# 01_POWER.net
KiCad netlist of a schematic drawn in Altium Designer
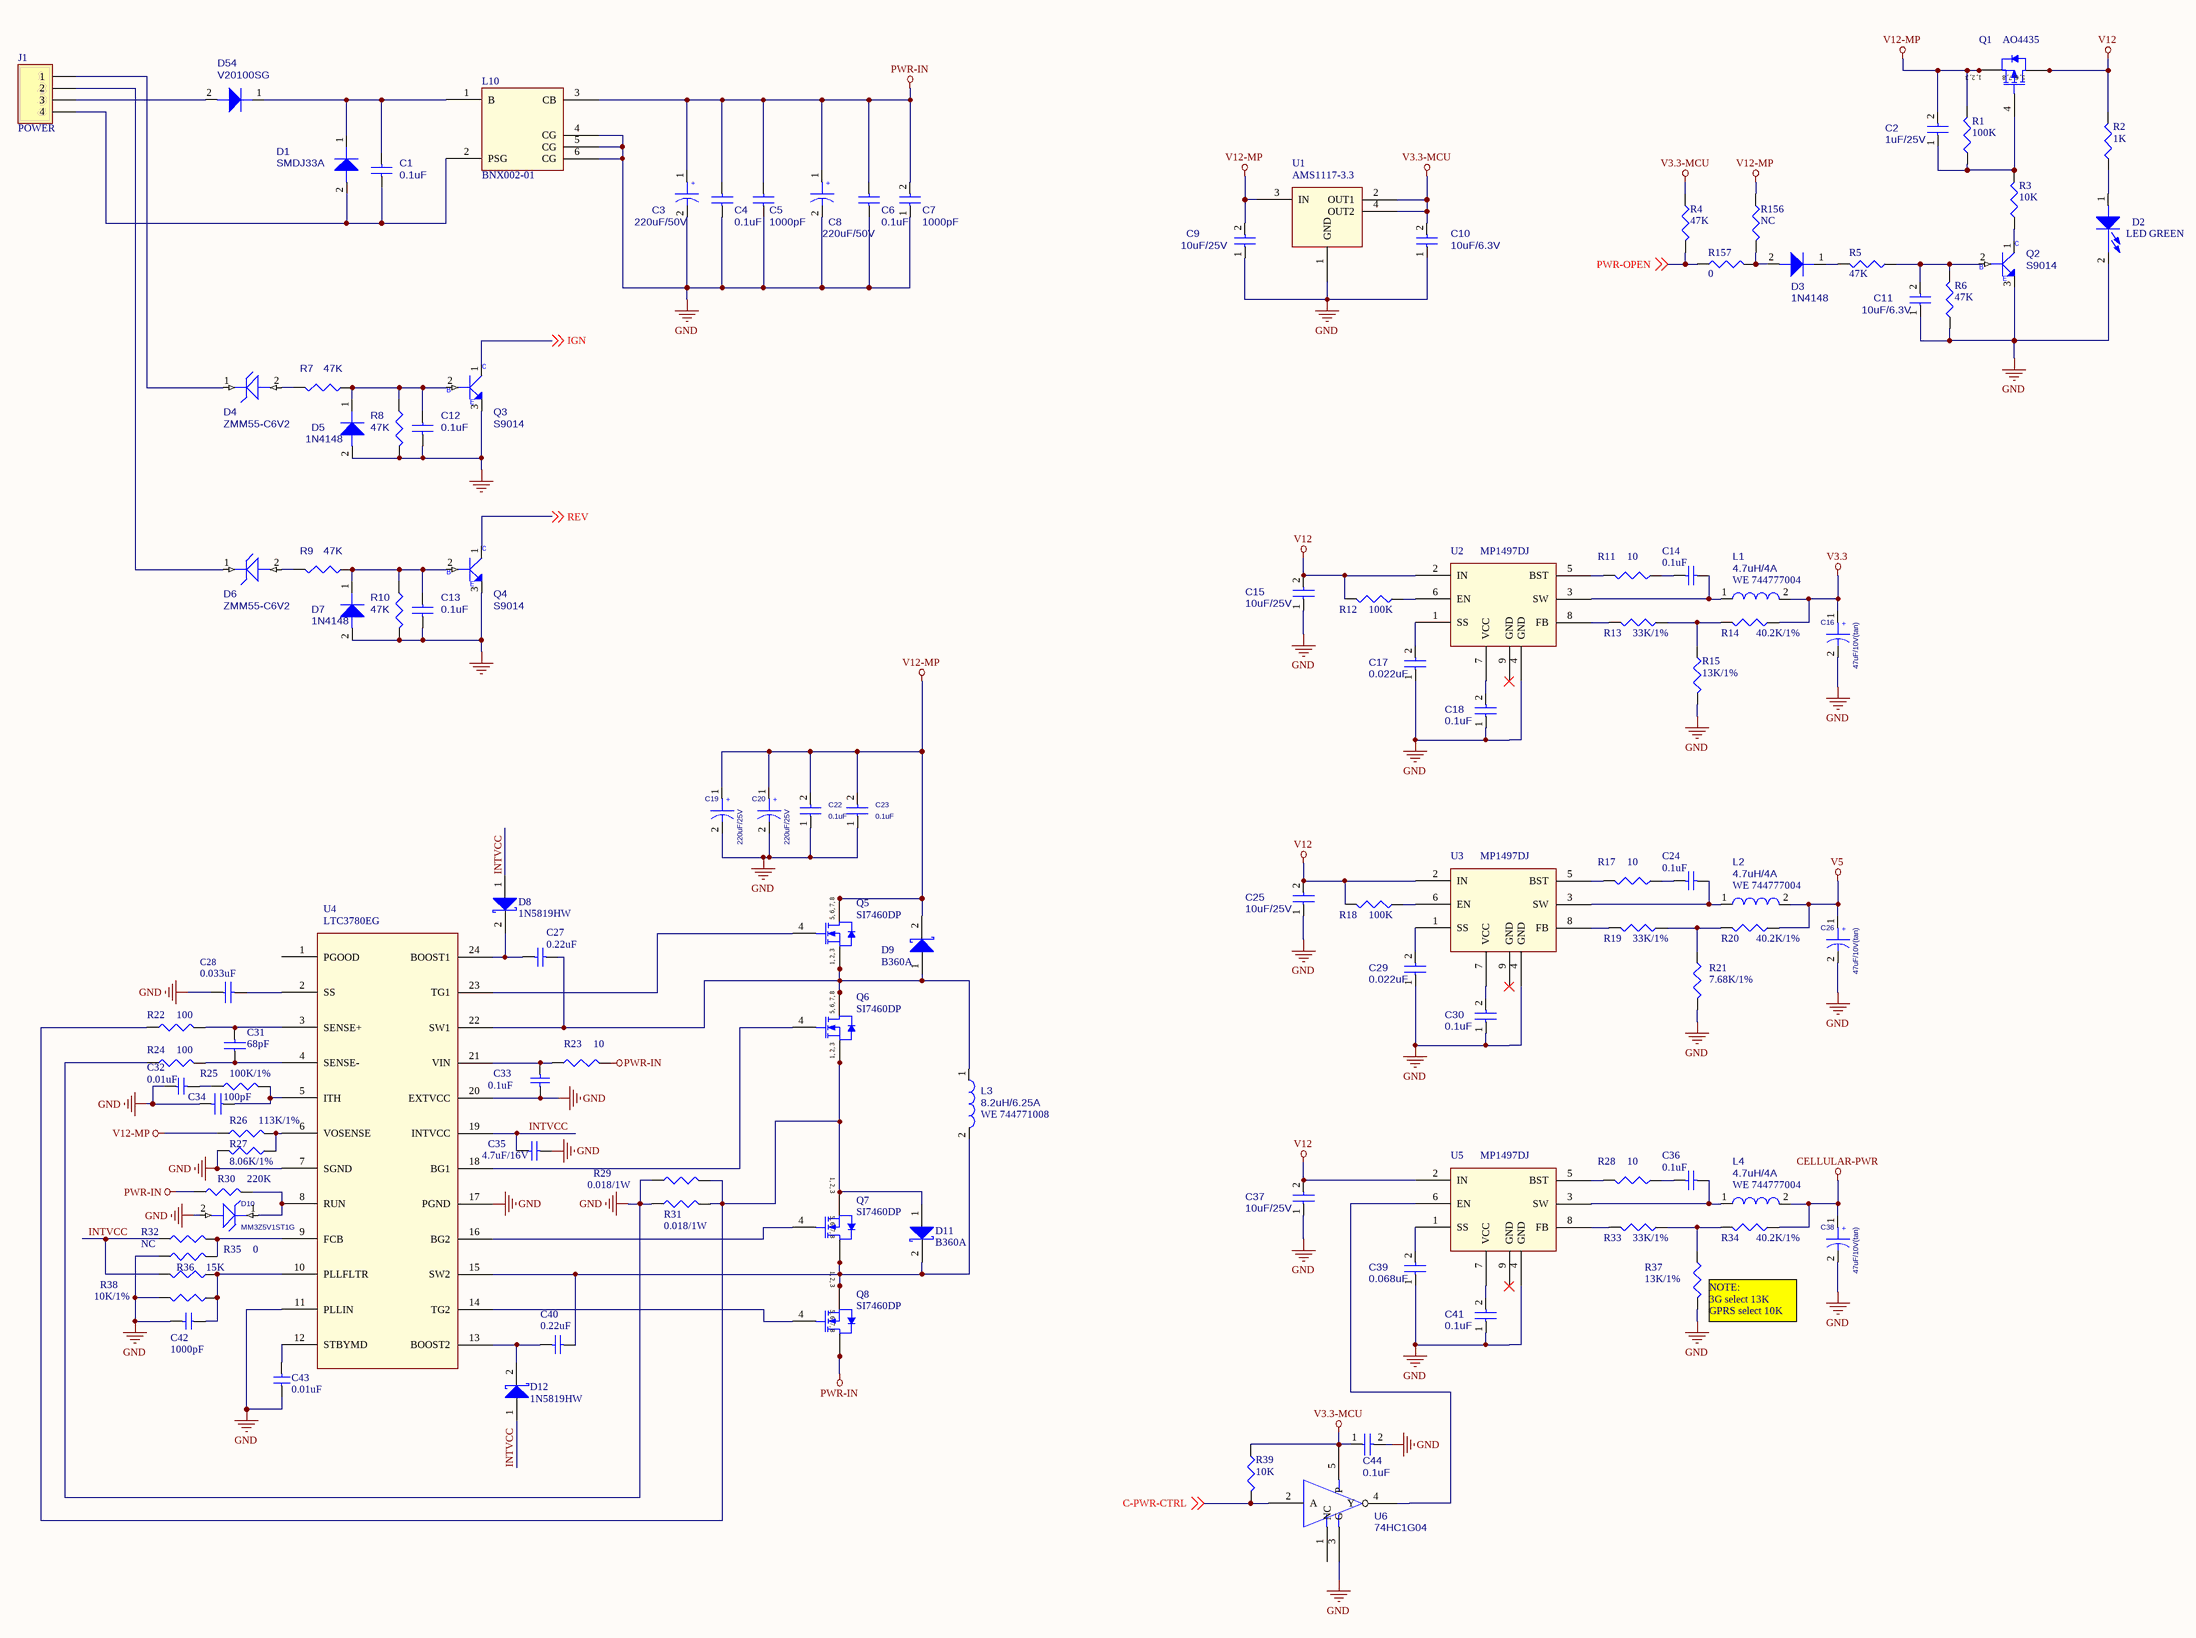
[diagram p0: [01]POWER.SchDoc]

(export (version "E")
  (design (tool "Eeschema 10.0.6"))
  (components
    (comp (ref "C1") (value "0.1uF") (libsource (lib "") (part "CAP NP_Dup2_1")))
    (comp (ref "C2") (value "1uF/25V") (footprint "0805") (libsource (lib "*") (part "CAP NP_Dup2")))
    (comp (ref "C3") (value "220uF/50V") (libsource (lib "*") (part "CAP WP")))
    (comp (ref "C4") (value "0.1uF") (libsource (lib "") (part "CAP NP_Dup2_1")))
    (comp (ref "C5") (value "1000pF") (libsource (lib "") (part "CAP NP_Dup2_1")))
    (comp (ref "C6") (value "0.1uF") (libsource (lib "") (part "CAP NP_Dup2_1")))
    (comp (ref "C7") (value "1000pF") (libsource (lib "*") (part "CAP NP_Dup2")))
    (comp (ref "C8") (value "220uF/50V") (libsource (lib "*") (part "CAP WP")))
    (comp (ref "C9") (value "10uF/25V") (footprint "1812") (libsource (lib "*") (part "CAP NP_Dup2")))
    (comp (ref "C10") (value "10uF/6.3V") (footprint "0805") (libsource (lib "*") (part "CAP NP_Dup2")))
    (comp (ref "C11") (value "10uF/6.3V") (footprint "0805") (libsource (lib "*") (part "CAP NP_Dup2")))
    (comp (ref "C12") (value "0.1uF") (libsource (lib "*") (part "CAP")))
    (comp (ref "C13") (value "0.1uF") (libsource (lib "*") (part "CAP")))
    (comp (ref "C14")
      (value "0.1uF")
      (footprint "0603")
      (description "Capacitor")
      (libsource (lib "Miscellaneous Devices") (part "Cap"))
    )
    (comp (ref "C15") (value "10uF/25V") (footprint "1812") (libsource (lib "*") (part "CAP NP_Dup2")))
    (comp (ref "C16") (value "47uF/10V(tan)") (footprint "3528") (libsource (lib "*") (part "CAP WP")))
    (comp (ref "C17") (value "0.022uF") (footprint "0603") (libsource (lib "*") (part "CAP NP_Dup2")))
    (comp (ref "C18") (value "0.1uF") (footprint "0603") (libsource (lib "*") (part "CAP NP_Dup2")))
    (comp (ref "C19") (value "220uF/25V") (footprint "DL-8*10.5") (libsource (lib "*") (part "CAP WP")))
    (comp (ref "C20") (value "220uF/25V") (footprint "DL-8*10.5") (libsource (lib "*") (part "CAP WP")))
    (comp (ref "C22") (value "0.1uF") (libsource (lib "*") (part "CAP NP_Dup2")))
    (comp (ref "C23") (value "0.1uF") (libsource (lib "*") (part "CAP NP_Dup2")))
    (comp (ref "C24")
      (value "0.1uF")
      (footprint "0603")
      (description "Capacitor")
      (libsource (lib "Miscellaneous Devices") (part "Cap"))
    )
    (comp (ref "C25") (value "10uF/25V") (footprint "1812") (libsource (lib "*") (part "CAP NP_Dup2")))
    (comp (ref "C26") (value "47uF/10V(tan)") (footprint "3528") (libsource (lib "*") (part "CAP WP")))
    (comp (ref "C27")
      (value "0.22uF")
      (footprint "0603")
      (description "Capacitor")
      (libsource (lib "Miscellaneous Devices") (part "Cap"))
    )
    (comp (ref "C28") (value "0.033uF") (footprint "0603") (libsource (lib "*") (part "06033C223KAT1A_0")))
    (comp (ref "C29") (value "0.022uF") (footprint "0603") (libsource (lib "*") (part "CAP NP_Dup2")))
    (comp (ref "C30") (value "0.1uF") (footprint "0603") (libsource (lib "*") (part "CAP NP_Dup2")))
    (comp (ref "C31") (value "68pF") (footprint "0603") (libsource (lib "*") (part "06033C223KAT1A_0")))
    (comp (ref "C32") (value "0.01uF") (footprint "0603") (libsource (lib "*") (part "06033C103KAT2A")))
    (comp (ref "C33")
      (value "0.1uF")
      (footprint "0603")
      (description "Capacitor")
      (libsource (lib "Miscellaneous Devices") (part "Cap"))
    )
    (comp (ref "C34") (value "100pF") (footprint "0603") (libsource (lib "*") (part "06035A470KAT1A_0")))
    (comp (ref "C35")
      (value "4.7uF/16V")
      (footprint "0805")
      (description "Capacitor")
      (libsource (lib "Miscellaneous Devices") (part "Cap"))
    )
    (comp (ref "C36")
      (value "0.1uF")
      (footprint "0603")
      (description "Capacitor")
      (libsource (lib "Miscellaneous Devices") (part "Cap"))
    )
    (comp (ref "C37") (value "10uF/25V") (footprint "1812") (libsource (lib "*") (part "CAP NP_Dup2")))
    (comp (ref "C38") (value "47uF/10V(tan)") (footprint "3528") (libsource (lib "*") (part "CAP WP")))
    (comp (ref "C39") (value "0.068uF") (footprint "0603") (libsource (lib "*") (part "CAP NP_Dup2")))
    (comp (ref "C40")
      (value "0.22uF")
      (footprint "0603")
      (description "Capacitor")
      (libsource (lib "Miscellaneous Devices") (part "Cap"))
    )
    (comp (ref "C41") (value "0.1uF") (footprint "0603") (libsource (lib "*") (part "CAP NP_Dup2")))
    (comp (ref "C42") (value "1000pF") (footprint "0603") (libsource (lib "*") (part "06033C103KAT2A_0")))
    (comp (ref "C43") (value "0.01uF") (footprint "0603") (libsource (lib "*") (part "06033C103KAT2A_0")))
    (comp (ref "C44") (value "0.1uF") (footprint "0603") (libsource (lib "*") (part "CAP NP_Dup2")))
    (comp (ref "D1")
      (value "SMDJ33A")
      (footprint "DO214AB")
      (libsource (lib "*") (part "1N4148WS-7-F_SOD323-2"))
    )
    (comp (ref "D2") (value "LED GREEN") (footprint "LED0603") (libsource (lib "*") (part "LN01401_1")))
    (comp (ref "D3")
      (value "1N4148")
      (footprint "MINI-MELF")
      (libsource (lib "*") (part "1N4148WS-7-F_SOD323-2"))
    )
    (comp (ref "D4")
      (value "ZMM55-C6V2")
      (footprint "MINI-MELF")
      (libsource (lib "*") (part "MMGZ5231BPTLL34"))
    )
    (comp (ref "D5")
      (value "1N4148")
      (footprint "MINI-MELF")
      (libsource (lib "*") (part "1N4148WS-7-F_SOD323-2"))
    )
    (comp (ref "D6")
      (value "ZMM55-C6V2")
      (footprint "MINI-MELF")
      (libsource (lib "*") (part "MMGZ5231BPTLL34"))
    )
    (comp (ref "D7")
      (value "1N4148")
      (footprint "MINI-MELF")
      (libsource (lib "*") (part "1N4148WS-7-F_SOD323-2"))
    )
    (comp (ref "D8")
      (value "1N5819HW")
      (footprint "1N5819")
      (description "Schottky Rectifier")
      (libsource (lib "Miscellaneous Devices") (part "Diode 11DQ03"))
    )
    (comp (ref "D9")
      (value "B360A")
      (footprint "B320A")
      (description "Schottky Rectifier")
      (libsource (lib "Miscellaneous Devices") (part "Diode 11DQ03"))
    )
    (comp (ref "D10")
      (value "MM3Z5V1ST1G")
      (footprint "MM3Z5V1ST1G")
      (libsource (lib "*") (part "MMGZ5231BPTLL34"))
    )
    (comp (ref "D11")
      (value "B360A")
      (footprint "B320A")
      (description "Schottky Rectifier")
      (libsource (lib "Miscellaneous Devices") (part "Diode 11DQ03"))
    )
    (comp (ref "D12")
      (value "1N5819HW")
      (footprint "1N5819")
      (description "Schottky Rectifier")
      (libsource (lib "Miscellaneous Devices") (part "Diode 11DQ03"))
    )
    (comp (ref "D54")
      (value "V20100SG")
      (footprint "V20100SG")
      (libsource (lib "*") (part "1N4148WS-7-F_SOD323-2"))
    )
    (comp (ref "J1")
      (value "POWER")
      (footprint "5557-4PIN")
      (description "Header, 4-Pin")
      (libsource (lib "Miscellaneous Connectors") (part "Header 4"))
    )
    (comp (ref "L1")
      (value "4.7uH/4A")
      (footprint "IND-4.7UH-4A")
      (fields (field (name "CODE") "WE 744777004"))
      (libsource (lib "*") (part "4.7UH_CDH2D09BNP-4R7MC_0.7A_20%"))
    )
    (comp (ref "L2")
      (value "4.7uH/4A")
      (footprint "IND-4.7UH-4A")
      (fields (field (name "CODE") "WE 744777004"))
      (libsource (lib "*") (part "4.7UH_CDH2D09BNP-4R7MC_0.7A_20%"))
    )
    (comp (ref "L3")
      (value "8.2uH/6.25A")
      (footprint "IND-8.2UH-10A")
      (fields (field (name "CODE") "WE 744771008"))
      (libsource (lib "*") (part "4.7UH_CDH2D09BNP-4R7MC_0.7A_20%"))
    )
    (comp (ref "L4")
      (value "4.7uH/4A")
      (footprint "IND-4.7UH-4A")
      (fields (field (name "CODE") "WE 744777004"))
      (libsource (lib "*") (part "4.7UH_CDH2D09BNP-4R7MC_0.7A_20%"))
    )
    (comp (ref "L10")
      (value "BNX002-01")
      (footprint "BNX002-001")
      (libsource (lib "Schlib") (part "BNX002-01"))
    )
    (comp (ref "Q1")
      (value "AO4435")
      (footprint "SO8")
      (description "P-Channel 30V (D-S)  MOSFET")
      (fields (field (name "PUBLISHER") "Altium Limited"))
      (libsource (lib "Vishay Siliconix Discrete MOSFET") (part "SI4431DY"))
    )
    (comp (ref "Q2")
      (value "S9014")
      (footprint "NPN")
      (fields (field (name "PART NUMBER") "SB039040000"))
      (libsource (lib "*") (part "MMBT3904_NL_SOT23-3"))
    )
    (comp (ref "Q3")
      (value "S9014")
      (footprint "NPN")
      (fields (field (name "PART NUMBER") "SB039040000"))
      (libsource (lib "*") (part "MMBT3904_NL_SOT23-3"))
    )
    (comp (ref "Q4") (value "S9014") (footprint "NPN") (libsource (lib "*") (part "MMBT3904_NL_SOT23-3")))
    (comp (ref "Q5")
      (value "SI7460DP")
      (footprint "POWERPAK")
      (description "N-Channel 30V (D-S)  MOSFET")
      (libsource (lib "Vishay Siliconix Discrete MOSFET") (part "SI4410DY"))
    )
    (comp (ref "Q6")
      (value "SI7460DP")
      (footprint "POWERPAK")
      (description "N-Channel 30V (D-S)  MOSFET")
      (libsource (lib "Vishay Siliconix Discrete MOSFET") (part "SI4410DY"))
    )
    (comp (ref "Q7")
      (value "SI7460DP")
      (footprint "POWERPAK")
      (description "N-Channel 30V (D-S)  MOSFET")
      (libsource (lib "Vishay Siliconix Discrete MOSFET") (part "SI4410DY"))
    )
    (comp (ref "Q8")
      (value "SI7460DP")
      (footprint "POWERPAK")
      (description "N-Channel 30V (D-S)  MOSFET")
      (libsource (lib "Vishay Siliconix Discrete MOSFET") (part "SI4410DY"))
    )
    (comp (ref "R1") (value "100K") (footprint "0603") (libsource (lib "*") (part "CR16-1003FM")))
    (comp (ref "R2") (value "1K") (footprint "0603") (libsource (lib "*") (part "CR16-1003FM")))
    (comp (ref "R3") (value "10K") (footprint "0603") (libsource (lib "*") (part "CR16-1003FM")))
    (comp (ref "R4") (value "47K") (footprint "0603") (libsource (lib "*") (part "CR16-1003FM")))
    (comp (ref "R5") (value "47K") (footprint "0603") (libsource (lib "*") (part "CR16-1003FM")))
    (comp (ref "R6") (value "47K") (footprint "0603") (libsource (lib "*") (part "CR16-1003FM")))
    (comp (ref "R7") (value "47K") (libsource (lib "*") (part "R")))
    (comp (ref "R8") (value "47K") (libsource (lib "*") (part "R")))
    (comp (ref "R9") (value "47K") (libsource (lib "*") (part "R")))
    (comp (ref "R10") (value "47K") (libsource (lib "*") (part "R")))
    (comp (ref "R11") (value "10") (footprint "0603") (libsource (lib "*") (part "CR16-1003FM")))
    (comp (ref "R12") (value "100K") (footprint "0603") (libsource (lib "*") (part "CR16-1003FM")))
    (comp (ref "R13") (value "33K/1%") (footprint "0603") (libsource (lib "*") (part "CR16-1003FM")))
    (comp (ref "R14") (value "40.2K/1%") (footprint "0603") (libsource (lib "*") (part "CR16-1003FM")))
    (comp (ref "R15") (value "13K/1%") (footprint "0603") (libsource (lib "*") (part "CR16-1003FM")))
    (comp (ref "R17") (value "10") (footprint "0603") (libsource (lib "*") (part "CR16-1003FM")))
    (comp (ref "R18") (value "100K") (footprint "0603") (libsource (lib "*") (part "CR16-1003FM")))
    (comp (ref "R19") (value "33K/1%") (footprint "0603") (libsource (lib "*") (part "CR16-1003FM")))
    (comp (ref "R20") (value "40.2K/1%") (footprint "0603") (libsource (lib "*") (part "CR16-1003FM")))
    (comp (ref "R21") (value "7.68K/1%") (footprint "0603") (libsource (lib "*") (part "CR16-1003FM")))
    (comp (ref "R22") (value "100") (footprint "0603") (libsource (lib "*") (part "CR16-1241FM")))
    (comp (ref "R23") (value "10") (footprint "0805") (libsource (lib "*") (part "CR16-1003FM")))
    (comp (ref "R24") (value "100") (footprint "0603") (libsource (lib "*") (part "CR16-1241FM")))
    (comp (ref "R25") (value "100K/1%") (footprint "0603") (libsource (lib "*") (part "CR16-1003FM")))
    (comp (ref "R26") (value "113K/1%") (footprint "0603") (libsource (lib "*") (part "CR16-1133FM")))
    (comp (ref "R27") (value "8.06K/1%") (footprint "0603") (libsource (lib "*") (part "CR16-8061FM")))
    (comp (ref "R28") (value "10") (footprint "0603") (libsource (lib "*") (part "CR16-1003FM")))
    (comp (ref "R29") (value "0.018/1W") (footprint "2512") (libsource (lib "*") (part "CR16-1003FM")))
    (comp (ref "R30") (value "220K") (footprint "0603") (libsource (lib "*") (part "CR16-224JM")))
    (comp (ref "R31") (value "0.018/1W") (footprint "2512") (libsource (lib "*") (part "CR16-1003FM")))
    (comp (ref "R32") (value "NC") (footprint "0603") (libsource (lib "*") (part "CR16-1003FM")))
    (comp (ref "R33") (value "33K/1%") (footprint "0603") (libsource (lib "*") (part "CR16-1003FM")))
    (comp (ref "R34") (value "40.2K/1%") (footprint "0603") (libsource (lib "*") (part "CR16-1003FM")))
    (comp (ref "R35") (value "0") (footprint "0603") (libsource (lib "*") (part "CR16-1003FM")))
    (comp (ref "R36") (value "15K") (footprint "0603") (libsource (lib "*") (part "CR16-1003FM")))
    (comp (ref "R37") (value "13K/1%") (footprint "0603") (libsource (lib "*") (part "CR16-1003FM")))
    (comp (ref "R38") (value "10K/1%") (footprint "0603") (libsource (lib "*") (part "CR16-1003FM")))
    (comp (ref "R39") (value "10K") (footprint "0603") (libsource (lib "*") (part "CR16-1003FM")))
    (comp (ref "R156") (value "NC") (footprint "0603") (libsource (lib "*") (part "CR16-1003FM")))
    (comp (ref "R157") (value "0") (footprint "0603") (libsource (lib "*") (part "CR16-1003FM")))
    (comp (ref "U1")
      (value "AMS1117-3.3")
      (footprint "AMS1117")
      (libsource (lib "*") (part "LT1963EST-1_4.8"))
    )
    (comp (ref "U2") (value "MP1497DJ") (footprint "TSOT23-8") (libsource (lib "*") (part "MP1482_5")))
    (comp (ref "U3") (value "MP1497DJ") (footprint "TSOT23-8") (libsource (lib "*") (part "MP1482_5")))
    (comp (ref "U4") (value "LTC3780EG") (footprint "LTC3780EG") (libsource (lib "*") (part "LTC3780EG")))
    (comp (ref "U5") (value "MP1497DJ") (footprint "TSOT23-8") (libsource (lib "*") (part "MP1482_5")))
    (comp (ref "U6") (value "74HC1G04") (libsource (lib "*") (part "74LVC1G04GW_SOT353-5")))
  )
  (nets
    (net (code "1") (name "/INTVCC") (class "Default")
      (node (ref "C35") (pin "1") (pinfunction "1_1") (pintype "passive"))
      (node (ref "D12") (pin "1") (pinfunction "A_1") (pintype "passive"))
      (node (ref "D8") (pin "1") (pinfunction "A_1") (pintype "passive"))
      (node (ref "R32") (pin "1") (pinfunction "1_1") (pintype "passive"))
      (node (ref "R36") (pin "2") (pinfunction "2_2") (pintype "passive"))
      (node (ref "U4") (pin "19") (pinfunction "INTVCC_19") (pintype "passive"))
    )
    (net (code "2") (name "C-PWR-CTRL") (class "Default")
      (node (ref "R39") (pin "2") (pinfunction "2_2") (pintype "passive"))
      (node (ref "U6") (pin "2") (pinfunction "A_2") (pintype "passive"))
    )
    (net (code "3") (name "CELLULAR-PWR") (class "Default")
      (node (ref "C38") (pin "1") (pinfunction "1_1") (pintype "passive"))
      (node (ref "L4") (pin "2") (pinfunction "2_2") (pintype "passive"))
      (node (ref "R34") (pin "1") (pinfunction "1_1") (pintype "passive"))
    )
    (net (code "4") (name "GND") (class "Default")
      (node (ref "C10") (pin "1") (pinfunction "1_1") (pintype "passive"))
      (node (ref "C11") (pin "1") (pinfunction "1_1") (pintype "passive"))
      (node (ref "C12") (pin "2") (pinfunction "2_2") (pintype "passive"))
      (node (ref "C13") (pin "2") (pinfunction "2_2") (pintype "passive"))
      (node (ref "C15") (pin "1") (pinfunction "1_1") (pintype "passive"))
      (node (ref "C16") (pin "2") (pinfunction "2_2") (pintype "passive"))
      (node (ref "C17") (pin "1") (pinfunction "1_1") (pintype "passive"))
      (node (ref "C18") (pin "1") (pinfunction "1_1") (pintype "passive"))
      (node (ref "C19") (pin "2") (pinfunction "2_2") (pintype "passive"))
      (node (ref "C20") (pin "2") (pinfunction "2_2") (pintype "passive"))
      (node (ref "C22") (pin "1") (pinfunction "1_1") (pintype "passive"))
      (node (ref "C23") (pin "1") (pinfunction "1_1") (pintype "passive"))
      (node (ref "C25") (pin "1") (pinfunction "1_1") (pintype "passive"))
      (node (ref "C26") (pin "2") (pinfunction "2_2") (pintype "passive"))
      (node (ref "C28") (pin "1") (pinfunction "1_1") (pintype "passive"))
      (node (ref "C29") (pin "1") (pinfunction "1_1") (pintype "passive"))
      (node (ref "C3") (pin "2") (pinfunction "2_2") (pintype "passive"))
      (node (ref "C30") (pin "1") (pinfunction "1_1") (pintype "passive"))
      (node (ref "C32") (pin "1") (pinfunction "1_1") (pintype "passive"))
      (node (ref "C33") (pin "1") (pinfunction "1_1") (pintype "passive"))
      (node (ref "C34") (pin "2") (pinfunction "2_2") (pintype "passive"))
      (node (ref "C35") (pin "2") (pinfunction "2_2") (pintype "passive"))
      (node (ref "C37") (pin "1") (pinfunction "1_1") (pintype "passive"))
      (node (ref "C38") (pin "2") (pinfunction "2_2") (pintype "passive"))
      (node (ref "C39") (pin "1") (pinfunction "1_1") (pintype "passive"))
      (node (ref "C4") (pin "1") (pinfunction "1_1") (pintype "passive"))
      (node (ref "C41") (pin "1") (pinfunction "1_1") (pintype "passive"))
      (node (ref "C42") (pin "2") (pinfunction "2_2") (pintype "passive"))
      (node (ref "C43") (pin "1") (pinfunction "1_1") (pintype "passive"))
      (node (ref "C44") (pin "2") (pinfunction "2_2") (pintype "passive"))
      (node (ref "C5") (pin "1") (pinfunction "1_1") (pintype "passive"))
      (node (ref "C6") (pin "1") (pinfunction "1_1") (pintype "passive"))
      (node (ref "C7") (pin "1") (pinfunction "1_1") (pintype "passive"))
      (node (ref "C8") (pin "2") (pinfunction "2_2") (pintype "passive"))
      (node (ref "C9") (pin "1") (pinfunction "1_1") (pintype "passive"))
      (node (ref "D10") (pin "2") (pinfunction "2_2") (pintype "input"))
      (node (ref "D2") (pin "2") (pinfunction "CATHODE_2") (pintype "passive"))
      (node (ref "D5") (pin "2") (pinfunction "2_2") (pintype "passive"))
      (node (ref "D7") (pin "2") (pinfunction "2_2") (pintype "passive"))
      (node (ref "L10") (pin "4") (pinfunction "CG_4") (pintype "passive"))
      (node (ref "L10") (pin "5") (pinfunction "CG_5") (pintype "passive"))
      (node (ref "L10") (pin "6") (pinfunction "CG_6") (pintype "passive"))
      (node (ref "Q2") (pin "3") (pinfunction "EMITTER_3") (pintype "passive"))
      (node (ref "Q3") (pin "3") (pinfunction "EMITTER_3") (pintype "passive"))
      (node (ref "Q4") (pin "3") (pinfunction "EMITTER_3") (pintype "passive"))
      (node (ref "R10") (pin "2") (pinfunction "2_2") (pintype "passive"))
      (node (ref "R15") (pin "2") (pinfunction "2_2") (pintype "passive"))
      (node (ref "R21") (pin "2") (pinfunction "2_2") (pintype "passive"))
      (node (ref "R24") (pin "1") (pinfunction "1_1") (pintype "passive"))
      (node (ref "R27") (pin "2") (pinfunction "2_2") (pintype "passive"))
      (node (ref "R29") (pin "1") (pinfunction "1_1") (pintype "passive"))
      (node (ref "R31") (pin "1") (pinfunction "1_1") (pintype "passive"))
      (node (ref "R35") (pin "1") (pinfunction "1_1") (pintype "passive"))
      (node (ref "R37") (pin "2") (pinfunction "2_2") (pintype "passive"))
      (node (ref "R38") (pin "2") (pinfunction "2_2") (pintype "passive"))
      (node (ref "R6") (pin "1") (pinfunction "1_1") (pintype "passive"))
      (node (ref "R8") (pin "2") (pinfunction "2_2") (pintype "passive"))
      (node (ref "U1") (pin "1") (pinfunction "GND_1") (pintype "passive"))
      (node (ref "U2") (pin "4") (pinfunction "GND_4") (pintype "power_in"))
      (node (ref "U3") (pin "4") (pinfunction "GND_4") (pintype "power_in"))
      (node (ref "U4") (pin "11") (pinfunction "PLLIN_11") (pintype "passive"))
      (node (ref "U4") (pin "17") (pinfunction "PGND_17") (pintype "passive"))
      (node (ref "U4") (pin "20") (pinfunction "EXTVCC_20") (pintype "passive"))
      (node (ref "U4") (pin "7") (pinfunction "SGND_7") (pintype "passive"))
      (node (ref "U5") (pin "4") (pinfunction "GND_4") (pintype "power_in"))
      (node (ref "U6") (pin "3") (pinfunction "G_3") (pintype "passive"))
    )
    (net (code "5") (name "IGN") (class "Default")
      (node (ref "Q3") (pin "1") (pinfunction "COLLECTOR_1") (pintype "passive"))
    )
    (net (code "6") (name "Net-(C14-Pad2)") (class "Default")
      (node (ref "C14") (pin "2") (pinfunction "2_2") (pintype "passive"))
      (node (ref "R11") (pin "1") (pinfunction "1_1") (pintype "passive"))
    )
    (net (code "7") (name "Net-(C24-Pad2)") (class "Default")
      (node (ref "C24") (pin "2") (pinfunction "2_2") (pintype "passive"))
      (node (ref "R17") (pin "1") (pinfunction "1_1") (pintype "passive"))
    )
    (net (code "8") (name "Net-(C32-Pad2)") (class "Default")
      (node (ref "C32") (pin "2") (pinfunction "2_2") (pintype "passive"))
      (node (ref "R25") (pin "1") (pinfunction "1_1") (pintype "passive"))
    )
    (net (code "9") (name "Net-(C36-Pad2)") (class "Default")
      (node (ref "C36") (pin "2") (pinfunction "2_2") (pintype "passive"))
      (node (ref "R28") (pin "1") (pinfunction "1_1") (pintype "passive"))
    )
    (net (code "10") (name "Net-(D2-ANODE)") (class "Default")
      (node (ref "D2") (pin "1") (pinfunction "ANODE_1") (pintype "passive"))
      (node (ref "R2") (pin "1") (pinfunction "1_1") (pintype "passive"))
    )
    (net (code "11") (name "Net-(D3-Pad1)") (class "Default")
      (node (ref "D3") (pin "1") (pinfunction "1_1") (pintype "passive"))
      (node (ref "R5") (pin "2") (pinfunction "2_2") (pintype "passive"))
    )
    (net (code "12") (name "Net-(D3-Pad2)") (class "Default")
      (node (ref "D3") (pin "2") (pinfunction "2_2") (pintype "passive"))
      (node (ref "R156") (pin "2") (pinfunction "2_2") (pintype "passive"))
      (node (ref "R157") (pin "2") (pinfunction "2_2") (pintype "passive"))
    )
    (net (code "13") (name "Net-(D4-Pad1)") (class "Default")
      (node (ref "D4") (pin "1") (pinfunction "1_1") (pintype "input"))
      (node (ref "J1") (pin "1") (pinfunction "1_1") (pintype "passive"))
    )
    (net (code "14") (name "Net-(D4-Pad2)") (class "Default")
      (node (ref "D4") (pin "2") (pinfunction "2_2") (pintype "input"))
      (node (ref "R7") (pin "2") (pinfunction "2_2") (pintype "passive"))
    )
    (net (code "15") (name "Net-(D6-Pad1)") (class "Default")
      (node (ref "D6") (pin "1") (pinfunction "1_1") (pintype "input"))
      (node (ref "J1") (pin "2") (pinfunction "2_2") (pintype "passive"))
    )
    (net (code "16") (name "Net-(D6-Pad2)") (class "Default")
      (node (ref "D6") (pin "2") (pinfunction "2_2") (pintype "input"))
      (node (ref "R9") (pin "2") (pinfunction "2_2") (pintype "passive"))
    )
    (net (code "17") (name "Net-(D8-K)") (class "Default")
      (node (ref "C27") (pin "2") (pinfunction "2_2") (pintype "passive"))
      (node (ref "D8") (pin "2") (pinfunction "K_2") (pintype "passive"))
      (node (ref "U4") (pin "24") (pinfunction "BOOST1_24") (pintype "passive"))
    )
    (net (code "18") (name "Net-(D9-A)") (class "Default")
      (node (ref "C27") (pin "1") (pinfunction "1_1") (pintype "passive"))
      (node (ref "D9") (pin "1") (pinfunction "A_1") (pintype "passive"))
      (node (ref "L3") (pin "1") (pinfunction "1_1") (pintype "passive"))
      (node (ref "Q5") (pin "1") (pinfunction "S_1") (pintype "passive"))
      (node (ref "Q5") (pin "2") (pinfunction "S_2") (pintype "passive"))
      (node (ref "Q5") (pin "3") (pinfunction "S_3") (pintype "passive"))
      (node (ref "Q6") (pin "5") (pinfunction "D_5") (pintype "passive"))
      (node (ref "Q6") (pin "6") (pinfunction "D_6") (pintype "passive"))
      (node (ref "Q6") (pin "7") (pinfunction "D_7") (pintype "passive"))
      (node (ref "Q6") (pin "8") (pinfunction "D_8") (pintype "passive"))
      (node (ref "U4") (pin "22") (pinfunction "SW1_22") (pintype "passive"))
    )
    (net (code "19") (name "Net-(D11-A)") (class "Default")
      (node (ref "D11") (pin "1") (pinfunction "A_1") (pintype "passive"))
      (node (ref "Q6") (pin "1") (pinfunction "S_1") (pintype "passive"))
      (node (ref "Q6") (pin "2") (pinfunction "S_2") (pintype "passive"))
      (node (ref "Q6") (pin "3") (pinfunction "S_3") (pintype "passive"))
      (node (ref "Q7") (pin "1") (pinfunction "S_1") (pintype "passive"))
      (node (ref "Q7") (pin "2") (pinfunction "S_2") (pintype "passive"))
      (node (ref "Q7") (pin "3") (pinfunction "S_3") (pintype "passive"))
      (node (ref "R22") (pin "1") (pinfunction "1_1") (pintype "passive"))
      (node (ref "R29") (pin "2") (pinfunction "2_2") (pintype "passive"))
      (node (ref "R31") (pin "2") (pinfunction "2_2") (pintype "passive"))
    )
    (net (code "20") (name "Net-(D11-K)") (class "Default")
      (node (ref "C40") (pin "1") (pinfunction "1_1") (pintype "passive"))
      (node (ref "D11") (pin "2") (pinfunction "K_2") (pintype "passive"))
      (node (ref "L3") (pin "2") (pinfunction "2_2") (pintype "passive"))
      (node (ref "Q7") (pin "5") (pinfunction "D_5") (pintype "passive"))
      (node (ref "Q7") (pin "6") (pinfunction "D_6") (pintype "passive"))
      (node (ref "Q7") (pin "7") (pinfunction "D_7") (pintype "passive"))
      (node (ref "Q7") (pin "8") (pinfunction "D_8") (pintype "passive"))
      (node (ref "Q8") (pin "1") (pinfunction "S_1") (pintype "passive"))
      (node (ref "Q8") (pin "2") (pinfunction "S_2") (pintype "passive"))
      (node (ref "Q8") (pin "3") (pinfunction "S_3") (pintype "passive"))
      (node (ref "U4") (pin "15") (pinfunction "SW2_15") (pintype "passive"))
    )
    (net (code "21") (name "Net-(D12-K)") (class "Default")
      (node (ref "C40") (pin "2") (pinfunction "2_2") (pintype "passive"))
      (node (ref "D12") (pin "2") (pinfunction "K_2") (pintype "passive"))
      (node (ref "U4") (pin "13") (pinfunction "BOOST2_13") (pintype "passive"))
    )
    (net (code "22") (name "Net-(D54-Pad2)") (class "Default")
      (node (ref "D54") (pin "2") (pinfunction "2_2") (pintype "passive"))
      (node (ref "J1") (pin "3") (pinfunction "3_3") (pintype "passive"))
    )
    (net (code "23") (name "Net-(L10-B)") (class "Default")
      (node (ref "C1") (pin "2") (pinfunction "2_2") (pintype "passive"))
      (node (ref "D1") (pin "1") (pinfunction "1_1") (pintype "passive"))
      (node (ref "D54") (pin "1") (pinfunction "1_1") (pintype "passive"))
      (node (ref "L10") (pin "1") (pinfunction "B_1") (pintype "passive"))
    )
    (net (code "24") (name "Net-(L10-PSG)") (class "Default")
      (node (ref "C1") (pin "1") (pinfunction "1_1") (pintype "passive"))
      (node (ref "D1") (pin "2") (pinfunction "2_2") (pintype "passive"))
      (node (ref "J1") (pin "4") (pinfunction "4_4") (pintype "passive"))
      (node (ref "L10") (pin "2") (pinfunction "PSG_2") (pintype "passive"))
    )
    (net (code "25") (name "Net-(Q1-G)") (class "Default")
      (node (ref "C2") (pin "1") (pinfunction "1_1") (pintype "passive"))
      (node (ref "Q1") (pin "4") (pinfunction "G_4") (pintype "passive"))
      (node (ref "R1") (pin "1") (pinfunction "1_1") (pintype "passive"))
      (node (ref "R3") (pin "2") (pinfunction "2_2") (pintype "passive"))
    )
    (net (code "26") (name "Net-(Q2-BASE)") (class "Default")
      (node (ref "C11") (pin "2") (pinfunction "2_2") (pintype "passive"))
      (node (ref "Q2") (pin "2") (pinfunction "BASE_2") (pintype "input"))
      (node (ref "R5") (pin "1") (pinfunction "1_1") (pintype "passive"))
      (node (ref "R6") (pin "2") (pinfunction "2_2") (pintype "passive"))
    )
    (net (code "27") (name "Net-(Q2-COLLECTOR)") (class "Default")
      (node (ref "Q2") (pin "1") (pinfunction "COLLECTOR_1") (pintype "passive"))
      (node (ref "R3") (pin "1") (pinfunction "1_1") (pintype "passive"))
    )
    (net (code "28") (name "Net-(Q3-BASE)") (class "Default")
      (node (ref "C12") (pin "1") (pinfunction "1_1") (pintype "passive"))
      (node (ref "D5") (pin "1") (pinfunction "1_1") (pintype "passive"))
      (node (ref "Q3") (pin "2") (pinfunction "BASE_2") (pintype "input"))
      (node (ref "R7") (pin "1") (pinfunction "1_1") (pintype "passive"))
      (node (ref "R8") (pin "1") (pinfunction "1_1") (pintype "passive"))
    )
    (net (code "29") (name "Net-(Q4-BASE)") (class "Default")
      (node (ref "C13") (pin "1") (pinfunction "1_1") (pintype "passive"))
      (node (ref "D7") (pin "1") (pinfunction "1_1") (pintype "passive"))
      (node (ref "Q4") (pin "2") (pinfunction "BASE_2") (pintype "input"))
      (node (ref "R10") (pin "1") (pinfunction "1_1") (pintype "passive"))
      (node (ref "R9") (pin "1") (pinfunction "1_1") (pintype "passive"))
    )
    (net (code "30") (name "Net-(Q5-G)") (class "Default")
      (node (ref "Q5") (pin "4") (pinfunction "G_4") (pintype "passive"))
      (node (ref "U4") (pin "23") (pinfunction "TG1_23") (pintype "passive"))
    )
    (net (code "31") (name "Net-(Q6-G)") (class "Default")
      (node (ref "Q6") (pin "4") (pinfunction "G_4") (pintype "passive"))
      (node (ref "U4") (pin "18") (pinfunction "BG1_18") (pintype "passive"))
    )
    (net (code "32") (name "Net-(Q7-G)") (class "Default")
      (node (ref "Q7") (pin "4") (pinfunction "G_4") (pintype "passive"))
      (node (ref "U4") (pin "16") (pinfunction "BG2_16") (pintype "passive"))
    )
    (net (code "33") (name "Net-(Q8-G)") (class "Default")
      (node (ref "Q8") (pin "4") (pinfunction "G_4") (pintype "passive"))
      (node (ref "U4") (pin "14") (pinfunction "TG2_14") (pintype "passive"))
    )
    (net (code "34") (name "Net-(R13-Pad1)") (class "Default")
      (node (ref "R13") (pin "1") (pinfunction "1_1") (pintype "passive"))
      (node (ref "R14") (pin "2") (pinfunction "2_2") (pintype "passive"))
      (node (ref "R15") (pin "1") (pinfunction "1_1") (pintype "passive"))
    )
    (net (code "35") (name "Net-(R19-Pad1)") (class "Default")
      (node (ref "R19") (pin "1") (pinfunction "1_1") (pintype "passive"))
      (node (ref "R20") (pin "2") (pinfunction "2_2") (pintype "passive"))
      (node (ref "R21") (pin "1") (pinfunction "1_1") (pintype "passive"))
    )
    (net (code "36") (name "Net-(R33-Pad1)") (class "Default")
      (node (ref "R33") (pin "1") (pinfunction "1_1") (pintype "passive"))
      (node (ref "R34") (pin "2") (pinfunction "2_2") (pintype "passive"))
      (node (ref "R37") (pin "1") (pinfunction "1_1") (pintype "passive"))
    )
    (net (code "37") (name "Net-(U2-BST)") (class "Default")
      (node (ref "R11") (pin "2") (pinfunction "2_2") (pintype "passive"))
      (node (ref "U2") (pin "5") (pinfunction "BST_5") (pintype "passive"))
    )
    (net (code "38") (name "Net-(U2-EN)") (class "Default")
      (node (ref "R12") (pin "1") (pinfunction "1_1") (pintype "passive"))
      (node (ref "U2") (pin "6") (pinfunction "EN_6") (pintype "passive"))
    )
    (net (code "39") (name "Net-(U2-FB)") (class "Default")
      (node (ref "R13") (pin "2") (pinfunction "2_2") (pintype "passive"))
      (node (ref "U2") (pin "8") (pinfunction "FB_8") (pintype "passive"))
    )
    (net (code "40") (name "Net-(U2-SS)") (class "Default")
      (node (ref "C17") (pin "2") (pinfunction "2_2") (pintype "passive"))
      (node (ref "U2") (pin "1") (pinfunction "SS_1") (pintype "passive"))
    )
    (net (code "41") (name "Net-(U2-SW)") (class "Default")
      (node (ref "C14") (pin "1") (pinfunction "1_1") (pintype "passive"))
      (node (ref "L1") (pin "1") (pinfunction "1_1") (pintype "passive"))
      (node (ref "U2") (pin "3") (pinfunction "SW_3") (pintype "passive"))
    )
    (net (code "42") (name "Net-(U2-VCC)") (class "Default")
      (node (ref "C18") (pin "2") (pinfunction "2_2") (pintype "passive"))
      (node (ref "U2") (pin "7") (pinfunction "VCC_7") (pintype "passive"))
    )
    (net (code "43") (name "Net-(U3-BST)") (class "Default")
      (node (ref "R17") (pin "2") (pinfunction "2_2") (pintype "passive"))
      (node (ref "U3") (pin "5") (pinfunction "BST_5") (pintype "passive"))
    )
    (net (code "44") (name "Net-(U3-EN)") (class "Default")
      (node (ref "R18") (pin "1") (pinfunction "1_1") (pintype "passive"))
      (node (ref "U3") (pin "6") (pinfunction "EN_6") (pintype "passive"))
    )
    (net (code "45") (name "Net-(U3-FB)") (class "Default")
      (node (ref "R19") (pin "2") (pinfunction "2_2") (pintype "passive"))
      (node (ref "U3") (pin "8") (pinfunction "FB_8") (pintype "passive"))
    )
    (net (code "46") (name "Net-(U3-SS)") (class "Default")
      (node (ref "C29") (pin "2") (pinfunction "2_2") (pintype "passive"))
      (node (ref "U3") (pin "1") (pinfunction "SS_1") (pintype "passive"))
    )
    (net (code "47") (name "Net-(U3-SW)") (class "Default")
      (node (ref "C24") (pin "1") (pinfunction "1_1") (pintype "passive"))
      (node (ref "L2") (pin "1") (pinfunction "1_1") (pintype "passive"))
      (node (ref "U3") (pin "3") (pinfunction "SW_3") (pintype "passive"))
    )
    (net (code "48") (name "Net-(U3-VCC)") (class "Default")
      (node (ref "C30") (pin "2") (pinfunction "2_2") (pintype "passive"))
      (node (ref "U3") (pin "7") (pinfunction "VCC_7") (pintype "passive"))
    )
    (net (code "49") (name "Net-(U4-FCB)") (class "Default")
      (node (ref "R32") (pin "2") (pinfunction "2_2") (pintype "passive"))
      (node (ref "R35") (pin "2") (pinfunction "2_2") (pintype "passive"))
      (node (ref "U4") (pin "9") (pinfunction "FCB_9") (pintype "passive"))
    )
    (net (code "50") (name "Net-(U4-ITH)") (class "Default")
      (node (ref "C34") (pin "1") (pinfunction "1_1") (pintype "passive"))
      (node (ref "R25") (pin "2") (pinfunction "2_2") (pintype "passive"))
      (node (ref "U4") (pin "5") (pinfunction "ITH_5") (pintype "passive"))
    )
    (net (code "51") (name "Net-(U4-PLLFLTR)") (class "Default")
      (node (ref "C42") (pin "1") (pinfunction "1_1") (pintype "passive"))
      (node (ref "R36") (pin "1") (pinfunction "1_1") (pintype "passive"))
      (node (ref "R38") (pin "1") (pinfunction "1_1") (pintype "passive"))
      (node (ref "U4") (pin "10") (pinfunction "PLLFLTR_10") (pintype "passive"))
    )
    (net (code "52") (name "Net-(U4-RUN)") (class "Default")
      (node (ref "D10") (pin "1") (pinfunction "1_1") (pintype "input"))
      (node (ref "R30") (pin "2") (pinfunction "2_2") (pintype "passive"))
      (node (ref "U4") (pin "8") (pinfunction "RUN_8") (pintype "passive"))
    )
    (net (code "53") (name "Net-(U4-SENSE+)") (class "Default")
      (node (ref "C31") (pin "2") (pinfunction "2_2") (pintype "passive"))
      (node (ref "R22") (pin "2") (pinfunction "2_2") (pintype "passive"))
      (node (ref "U4") (pin "3") (pinfunction "SENSE+_3") (pintype "passive"))
    )
    (net (code "54") (name "Net-(U4-SENSE-)") (class "Default")
      (node (ref "C31") (pin "1") (pinfunction "1_1") (pintype "passive"))
      (node (ref "R24") (pin "2") (pinfunction "2_2") (pintype "passive"))
      (node (ref "U4") (pin "4") (pinfunction "SENSE-_4") (pintype "passive"))
    )
    (net (code "55") (name "Net-(U4-SS)") (class "Default")
      (node (ref "C28") (pin "2") (pinfunction "2_2") (pintype "passive"))
      (node (ref "U4") (pin "2") (pinfunction "SS_2") (pintype "passive"))
    )
    (net (code "56") (name "Net-(U4-STBYMD)") (class "Default")
      (node (ref "C43") (pin "2") (pinfunction "2_2") (pintype "passive"))
      (node (ref "U4") (pin "12") (pinfunction "STBYMD_12") (pintype "passive"))
    )
    (net (code "57") (name "Net-(U4-VIN)") (class "Default")
      (node (ref "C33") (pin "2") (pinfunction "2_2") (pintype "passive"))
      (node (ref "R23") (pin "1") (pinfunction "1_1") (pintype "passive"))
      (node (ref "U4") (pin "21") (pinfunction "VIN_21") (pintype "passive"))
    )
    (net (code "58") (name "Net-(U4-VOSENSE)") (class "Default")
      (node (ref "R26") (pin "2") (pinfunction "2_2") (pintype "passive"))
      (node (ref "R27") (pin "1") (pinfunction "1_1") (pintype "passive"))
      (node (ref "U4") (pin "6") (pinfunction "VOSENSE_6") (pintype "passive"))
    )
    (net (code "59") (name "Net-(U5-BST)") (class "Default")
      (node (ref "R28") (pin "2") (pinfunction "2_2") (pintype "passive"))
      (node (ref "U5") (pin "5") (pinfunction "BST_5") (pintype "passive"))
    )
    (net (code "60") (name "Net-(U5-EN)") (class "Default")
      (node (ref "U5") (pin "6") (pinfunction "EN_6") (pintype "passive"))
      (node (ref "U6") (pin "4") (pinfunction "Y_4") (pintype "passive"))
    )
    (net (code "61") (name "Net-(U5-FB)") (class "Default")
      (node (ref "R33") (pin "2") (pinfunction "2_2") (pintype "passive"))
      (node (ref "U5") (pin "8") (pinfunction "FB_8") (pintype "passive"))
    )
    (net (code "62") (name "Net-(U5-SS)") (class "Default")
      (node (ref "C39") (pin "2") (pinfunction "2_2") (pintype "passive"))
      (node (ref "U5") (pin "1") (pinfunction "SS_1") (pintype "passive"))
    )
    (net (code "63") (name "Net-(U5-SW)") (class "Default")
      (node (ref "C36") (pin "1") (pinfunction "1_1") (pintype "passive"))
      (node (ref "L4") (pin "1") (pinfunction "1_1") (pintype "passive"))
      (node (ref "U5") (pin "3") (pinfunction "SW_3") (pintype "passive"))
    )
    (net (code "64") (name "Net-(U5-VCC)") (class "Default")
      (node (ref "C41") (pin "2") (pinfunction "2_2") (pintype "passive"))
      (node (ref "U5") (pin "7") (pinfunction "VCC_7") (pintype "passive"))
    )
    (net (code "65") (name "PWR-IN") (class "Default")
      (node (ref "C3") (pin "1") (pinfunction "1_1") (pintype "passive"))
      (node (ref "C4") (pin "2") (pinfunction "2_2") (pintype "passive"))
      (node (ref "C5") (pin "2") (pinfunction "2_2") (pintype "passive"))
      (node (ref "C6") (pin "2") (pinfunction "2_2") (pintype "passive"))
      (node (ref "C7") (pin "2") (pinfunction "2_2") (pintype "passive"))
      (node (ref "C8") (pin "1") (pinfunction "1_1") (pintype "passive"))
      (node (ref "L10") (pin "3") (pinfunction "CB_3") (pintype "passive"))
      (node (ref "Q8") (pin "5") (pinfunction "D_5") (pintype "passive"))
      (node (ref "Q8") (pin "6") (pinfunction "D_6") (pintype "passive"))
      (node (ref "Q8") (pin "7") (pinfunction "D_7") (pintype "passive"))
      (node (ref "Q8") (pin "8") (pinfunction "D_8") (pintype "passive"))
      (node (ref "R23") (pin "2") (pinfunction "2_2") (pintype "passive"))
      (node (ref "R30") (pin "1") (pinfunction "1_1") (pintype "passive"))
    )
    (net (code "66") (name "PWR-OPEN") (class "Default")
      (node (ref "R157") (pin "1") (pinfunction "1_1") (pintype "passive"))
      (node (ref "R4") (pin "2") (pinfunction "2_2") (pintype "passive"))
    )
    (net (code "67") (name "REV") (class "Default")
      (node (ref "Q4") (pin "1") (pinfunction "COLLECTOR_1") (pintype "passive"))
    )
    (net (code "68") (name "V3.3") (class "Default")
      (node (ref "C16") (pin "1") (pinfunction "1_1") (pintype "passive"))
      (node (ref "L1") (pin "2") (pinfunction "2_2") (pintype "passive"))
      (node (ref "R14") (pin "1") (pinfunction "1_1") (pintype "passive"))
    )
    (net (code "69") (name "V3.3-MCU") (class "Default")
      (node (ref "C10") (pin "2") (pinfunction "2_2") (pintype "passive"))
      (node (ref "C44") (pin "1") (pinfunction "1_1") (pintype "passive"))
      (node (ref "R39") (pin "1") (pinfunction "1_1") (pintype "passive"))
      (node (ref "R4") (pin "1") (pinfunction "1_1") (pintype "passive"))
      (node (ref "U1") (pin "2") (pinfunction "OUT1_2") (pintype "passive"))
      (node (ref "U1") (pin "4") (pinfunction "OUT2_4") (pintype "passive"))
      (node (ref "U6") (pin "5") (pinfunction "P_5") (pintype "passive"))
    )
    (net (code "70") (name "V5") (class "Default")
      (node (ref "C26") (pin "1") (pinfunction "1_1") (pintype "passive"))
      (node (ref "L2") (pin "2") (pinfunction "2_2") (pintype "passive"))
      (node (ref "R20") (pin "1") (pinfunction "1_1") (pintype "passive"))
    )
    (net (code "71") (name "V12") (class "Default")
      (node (ref "C15") (pin "2") (pinfunction "2_2") (pintype "passive"))
      (node (ref "C25") (pin "2") (pinfunction "2_2") (pintype "passive"))
      (node (ref "C37") (pin "2") (pinfunction "2_2") (pintype "passive"))
      (node (ref "Q1") (pin "5") (pinfunction "D_5") (pintype "passive"))
      (node (ref "Q1") (pin "6") (pinfunction "D_6") (pintype "passive"))
      (node (ref "Q1") (pin "7") (pinfunction "D_7") (pintype "passive"))
      (node (ref "Q1") (pin "8") (pinfunction "D_8") (pintype "passive"))
      (node (ref "R12") (pin "2") (pinfunction "2_2") (pintype "passive"))
      (node (ref "R18") (pin "2") (pinfunction "2_2") (pintype "passive"))
      (node (ref "R2") (pin "2") (pinfunction "2_2") (pintype "passive"))
      (node (ref "U2") (pin "2") (pinfunction "IN_2") (pintype "passive"))
      (node (ref "U3") (pin "2") (pinfunction "IN_2") (pintype "passive"))
      (node (ref "U5") (pin "2") (pinfunction "IN_2") (pintype "passive"))
    )
    (net (code "72") (name "V12-MP") (class "Default")
      (node (ref "C19") (pin "1") (pinfunction "1_1") (pintype "passive"))
      (node (ref "C2") (pin "2") (pinfunction "2_2") (pintype "passive"))
      (node (ref "C20") (pin "1") (pinfunction "1_1") (pintype "passive"))
      (node (ref "C22") (pin "2") (pinfunction "2_2") (pintype "passive"))
      (node (ref "C23") (pin "2") (pinfunction "2_2") (pintype "passive"))
      (node (ref "C9") (pin "2") (pinfunction "2_2") (pintype "passive"))
      (node (ref "D9") (pin "2") (pinfunction "K_2") (pintype "passive"))
      (node (ref "Q1") (pin "1") (pinfunction "S_1") (pintype "passive"))
      (node (ref "Q1") (pin "2") (pinfunction "S_2") (pintype "passive"))
      (node (ref "Q1") (pin "3") (pinfunction "S_3") (pintype "passive"))
      (node (ref "Q5") (pin "5") (pinfunction "D_5") (pintype "passive"))
      (node (ref "Q5") (pin "6") (pinfunction "D_6") (pintype "passive"))
      (node (ref "Q5") (pin "7") (pinfunction "D_7") (pintype "passive"))
      (node (ref "Q5") (pin "8") (pinfunction "D_8") (pintype "passive"))
      (node (ref "R1") (pin "2") (pinfunction "2_2") (pintype "passive"))
      (node (ref "R156") (pin "1") (pinfunction "1_1") (pintype "passive"))
      (node (ref "R26") (pin "1") (pinfunction "1_1") (pintype "passive"))
      (node (ref "U1") (pin "3") (pinfunction "IN_3") (pintype "passive"))
    )
    (net (code "73") (name "unconnected-(U2-GND-Pad9)") (class "Default")
      (node (ref "U2") (pin "9") (pinfunction "GND_9") (pintype "power_in+no_connect"))
    )
    (net (code "74") (name "unconnected-(U3-GND-Pad9)") (class "Default")
      (node (ref "U3") (pin "9") (pinfunction "GND_9") (pintype "power_in+no_connect"))
    )
    (net (code "75") (name "unconnected-(U4-PGOOD-Pad1)") (class "Default")
      (node (ref "U4") (pin "1") (pinfunction "PGOOD_1") (pintype "passive"))
    )
    (net (code "76") (name "unconnected-(U5-GND-Pad9)") (class "Default")
      (node (ref "U5") (pin "9") (pinfunction "GND_9") (pintype "power_in+no_connect"))
    )
    (net (code "77") (name "unconnected-(U6-NC-Pad1)") (class "Default")
      (node (ref "U6") (pin "1") (pinfunction "NC_1") (pintype "passive"))
    )
  )
)
